# DCVoltageConditioning.net
KiCad netlist of a schematic drawn in Altium Designer
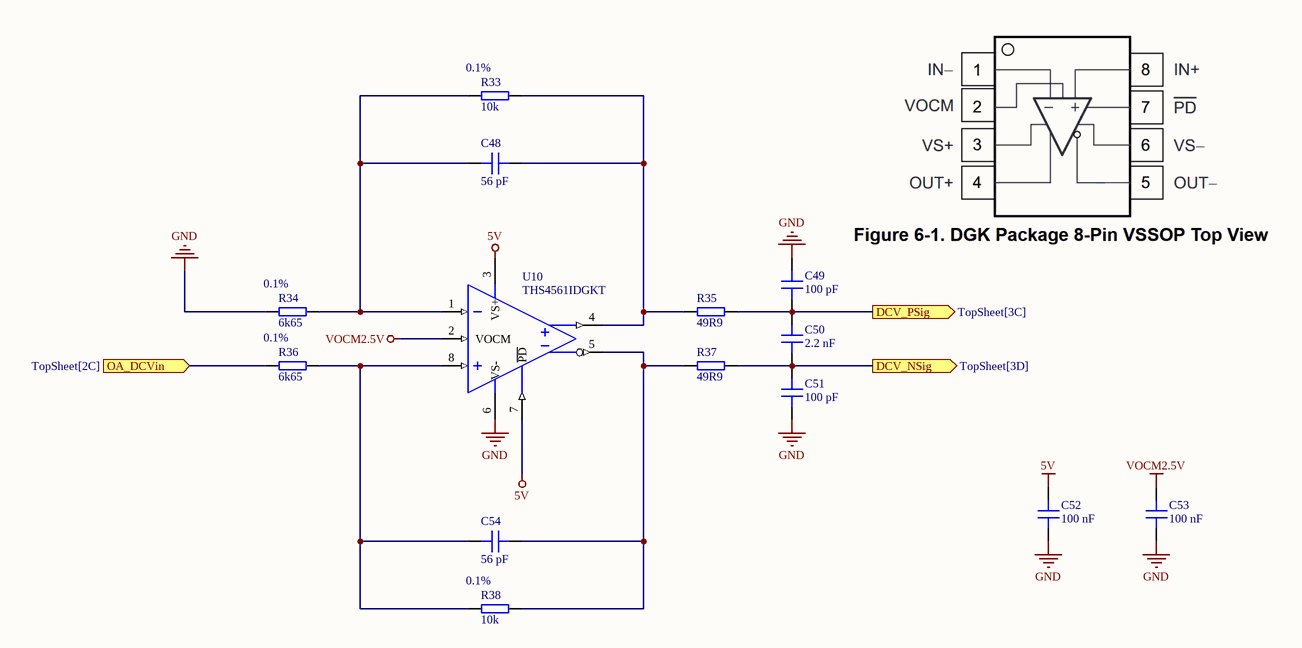
[diagram p0: DCVoltageConditioning.SchDoc]

(export (version "E")
  (design (tool "Eeschema 10.0.6"))
  (components
    (comp (ref "C48")
      (value "56 pF")
      (footprint "C_0603")
      (description "Capacitor 0603, 50 VDC, 56 pF, C0G")
      (fields
        (field (name "MANUFACTURER PART NUMBER") "CL10C560JB8NNNC")
        (field (name "MANUFACTURER") "Samsung Electro-Mechanics")
        (field (name "CREATED FROM") "DHufnagel")
      )
      (libsource (lib "user") (part "Capacitor"))
    )
    (comp (ref "C49")
      (value "100 pF")
      (footprint "C_0603_TE")
      (description "50V 100pF C0G ±5% 0603 Multilayer Ceramic Capacitors MLCC - SMD/SMT ROHS")
      (fields
        (field (name "MANUFACTURER PART NUMBER") "CL10C101JB8NNNC")
        (field (name "MANUFACTURER") "Samsung Electro-Mechanics")
        (field (name "CREATED FROM") "AGeiger")
      )
      (libsource (lib "user") (part "Capacitor"))
    )
    (comp (ref "C50")
      (value "2.2 nF")
      (footprint "C_0603")
      (description "Capacitor 0603, 50 VDC, 2.2 nF, X7R")
      (fields
        (field (name "MANUFACTURER PART NUMBER") "06035C222JAT2A")
        (field (name "MANUFACTURER") "AVX")
        (field (name "CREATED FROM") "MGremer")
      )
      (libsource (lib "user") (part "Capacitor"))
    )
    (comp (ref "C51")
      (value "100 pF")
      (footprint "C_0603_TE")
      (description "50V 100pF C0G ±5% 0603 Multilayer Ceramic Capacitors MLCC - SMD/SMT ROHS")
      (fields
        (field (name "MANUFACTURER PART NUMBER") "CL10C101JB8NNNC")
        (field (name "MANUFACTURER") "Samsung Electro-Mechanics")
        (field (name "CREATED FROM") "AGeiger")
      )
      (libsource (lib "user") (part "Capacitor"))
    )
    (comp (ref "C52")
      (value "100 nF")
      (footprint "C_0603")
      (description "Capacitor 0603, 50 VDC, 100nF, X7R")
      (fields
        (field (name "MANUFACTURER PART NUMBER") "C0603C104K5RAC3121")
        (field (name "MANUFACTURER") "KEMET")
        (field (name "CREATED FROM") "DHufnagel")
      )
      (libsource (lib "user") (part "Capacitor"))
    )
    (comp (ref "C53")
      (value "100 nF")
      (footprint "C_0603")
      (description "Capacitor 0603, 50 VDC, 100nF, X7R")
      (fields
        (field (name "MANUFACTURER PART NUMBER") "C0603C104K5RAC3121")
        (field (name "MANUFACTURER") "KEMET")
        (field (name "CREATED FROM") "DHufnagel")
      )
      (libsource (lib "user") (part "Capacitor"))
    )
    (comp (ref "C54")
      (value "56 pF")
      (footprint "C_0603")
      (description "Capacitor 0603, 50 VDC, 56 pF, C0G")
      (fields
        (field (name "MANUFACTURER PART NUMBER") "CL10C560JB8NNNC")
        (field (name "MANUFACTURER") "Samsung Electro-Mechanics")
        (field (name "CREATED FROM") "DHufnagel")
      )
      (libsource (lib "user") (part "Capacitor"))
    )
    (comp (ref "R33")
      (value "10k")
      (footprint "RES 0603_1608")
      (description "SMD resistor 0.1%, 10ppm")
      (fields
        (field (name "MANUFACTURER PART NUMBER") "ERA-3ARB103V")
        (field (name "MANUFACTURER") "Panasonic")
        (field (name "TOLERANCE") "0.1%")
        (field (name "CREATED FROM") "DHufnagel")
      )
      (libsource (lib "user") (part "Resistor"))
    )
    (comp (ref "R34")
      (value "6k65")
      (footprint "RES 0603_1608")
      (description "100mW Thin Film Resistor ±25ppm/℃ ±0.1% 6.65kΩ 0603 Chip Resistor - Surface Mount ROHS")
      (fields
        (field (name "MANUFACTURER PART NUMBER") "RT0603BRD076K65L")
        (field (name "MANUFACTURER") "YAGEO")
        (field (name "TOLERANCE") "0.1%")
        (field (name "CREATED FROM") "SPark")
      )
      (libsource (lib "user") (part "Resistor"))
    )
    (comp (ref "R35")
      (value "49R9")
      (footprint "RES 0603_1608")
      (description "SMD resistor 1%")
      (fields
        (field (name "MANUFACTURER PART NUMBER") "RK73H1JTTD49R9F")
        (field (name "MANUFACTURER") "KOA Speer")
        (field (name "CREATED FROM") "DHufnagel")
      )
      (libsource (lib "user") (part "Resistor"))
    )
    (comp (ref "R36")
      (value "6k65")
      (footprint "RES 0603_1608")
      (description "100mW Thin Film Resistor ±25ppm/℃ ±0.1% 6.65kΩ 0603 Chip Resistor - Surface Mount ROHS")
      (fields
        (field (name "MANUFACTURER PART NUMBER") "RT0603BRD076K65L")
        (field (name "MANUFACTURER") "YAGEO")
        (field (name "TOLERANCE") "0.1%")
        (field (name "CREATED FROM") "SPark")
      )
      (libsource (lib "user") (part "Resistor"))
    )
    (comp (ref "R37")
      (value "49R9")
      (footprint "RES 0603_1608")
      (description "SMD resistor 1%")
      (fields
        (field (name "MANUFACTURER PART NUMBER") "RK73H1JTTD49R9F")
        (field (name "MANUFACTURER") "KOA Speer")
        (field (name "CREATED FROM") "DHufnagel")
      )
      (libsource (lib "user") (part "Resistor"))
    )
    (comp (ref "R38")
      (value "10k")
      (footprint "RES 0603_1608")
      (description "SMD resistor 0.1%, 10ppm")
      (fields
        (field (name "MANUFACTURER PART NUMBER") "ERA-3ARB103V")
        (field (name "MANUFACTURER") "Panasonic")
        (field (name "TOLERANCE") "0.1%")
        (field (name "CREATED FROM") "DHufnagel")
      )
      (libsource (lib "user") (part "Resistor"))
    )
    (comp (ref "U10")
      (value "THS4561IDGKT")
      (footprint "SOP65P490X110-8N")
      (description "Fully Differential Amplifier, Low-Power, High Supply Range, 60-MHz")
      (fields
        (field (name "MANUFACTURER") "Texas Instruments")
        (field (name "LCSC PART NUMBER") "C2860980")
        (field (name "CREATED FROM") "DHufnagel")
      )
      (libsource (lib "user") (part "THS4561IDGKT"))
    )
  )
  (nets
    (net (code "1") (name "/DCV_NSig") (class "Default")
      (node (ref "C50") (pin "2") (pinfunction "2_2") (pintype "passive"))
      (node (ref "C51") (pin "1") (pinfunction "1_1") (pintype "passive"))
      (node (ref "R37") (pin "2") (pinfunction "2_2") (pintype "passive"))
    )
    (net (code "2") (name "/DCV_PSig") (class "Default")
      (node (ref "C49") (pin "2") (pinfunction "2_2") (pintype "passive"))
      (node (ref "C50") (pin "1") (pinfunction "1_1") (pintype "passive"))
      (node (ref "R35") (pin "2") (pinfunction "2_2") (pintype "passive"))
    )
    (net (code "3") (name "/OA_DCVin") (class "Default")
      (node (ref "R36") (pin "1") (pinfunction "1_1") (pintype "passive"))
    )
    (net (code "4") (name "5V") (class "Default")
      (node (ref "C52") (pin "1") (pinfunction "1_1") (pintype "passive"))
      (node (ref "U10") (pin "3") (pinfunction "VS+_3") (pintype "power_in"))
      (node (ref "U10") (pin "7") (pinfunction "~{PD}_7") (pintype "input"))
    )
    (net (code "5") (name "GND") (class "Default")
      (node (ref "C49") (pin "1") (pinfunction "1_1") (pintype "passive"))
      (node (ref "C51") (pin "2") (pinfunction "2_2") (pintype "passive"))
      (node (ref "C52") (pin "2") (pinfunction "2_2") (pintype "passive"))
      (node (ref "C53") (pin "2") (pinfunction "2_2") (pintype "passive"))
      (node (ref "R34") (pin "1") (pinfunction "1_1") (pintype "passive"))
      (node (ref "U10") (pin "6") (pinfunction "VS-_6") (pintype "power_in"))
    )
    (net (code "6") (name "Net-(U10-VIN+)") (class "Default")
      (node (ref "C54") (pin "1") (pinfunction "1_1") (pintype "passive"))
      (node (ref "R36") (pin "2") (pinfunction "2_2") (pintype "passive"))
      (node (ref "R38") (pin "1") (pinfunction "1_1") (pintype "passive"))
      (node (ref "U10") (pin "8") (pinfunction "VIN+_8") (pintype "input"))
    )
    (net (code "7") (name "Net-(U10-VIN-)") (class "Default")
      (node (ref "C48") (pin "1") (pinfunction "1_1") (pintype "passive"))
      (node (ref "R33") (pin "1") (pinfunction "1_1") (pintype "passive"))
      (node (ref "R34") (pin "2") (pinfunction "2_2") (pintype "passive"))
      (node (ref "U10") (pin "1") (pinfunction "VIN-_1") (pintype "input"))
    )
    (net (code "8") (name "Net-(U10-VOUT+)") (class "Default")
      (node (ref "C48") (pin "2") (pinfunction "2_2") (pintype "passive"))
      (node (ref "R33") (pin "2") (pinfunction "2_2") (pintype "passive"))
      (node (ref "R35") (pin "1") (pinfunction "1_1") (pintype "passive"))
      (node (ref "U10") (pin "4") (pinfunction "VOUT+_4") (pintype "output"))
    )
    (net (code "9") (name "Net-(U10-VOUT-)") (class "Default")
      (node (ref "C54") (pin "2") (pinfunction "2_2") (pintype "passive"))
      (node (ref "R37") (pin "1") (pinfunction "1_1") (pintype "passive"))
      (node (ref "R38") (pin "2") (pinfunction "2_2") (pintype "passive"))
      (node (ref "U10") (pin "5") (pinfunction "VOUT-_5") (pintype "output"))
    )
    (net (code "10") (name "VOCM2.5V") (class "Default")
      (node (ref "C53") (pin "1") (pinfunction "1_1") (pintype "passive"))
      (node (ref "U10") (pin "2") (pinfunction "VOCM_2") (pintype "input"))
    )
  )
)
